# MEMORY.net
KiCad netlist of a schematic drawn in Altium Designer
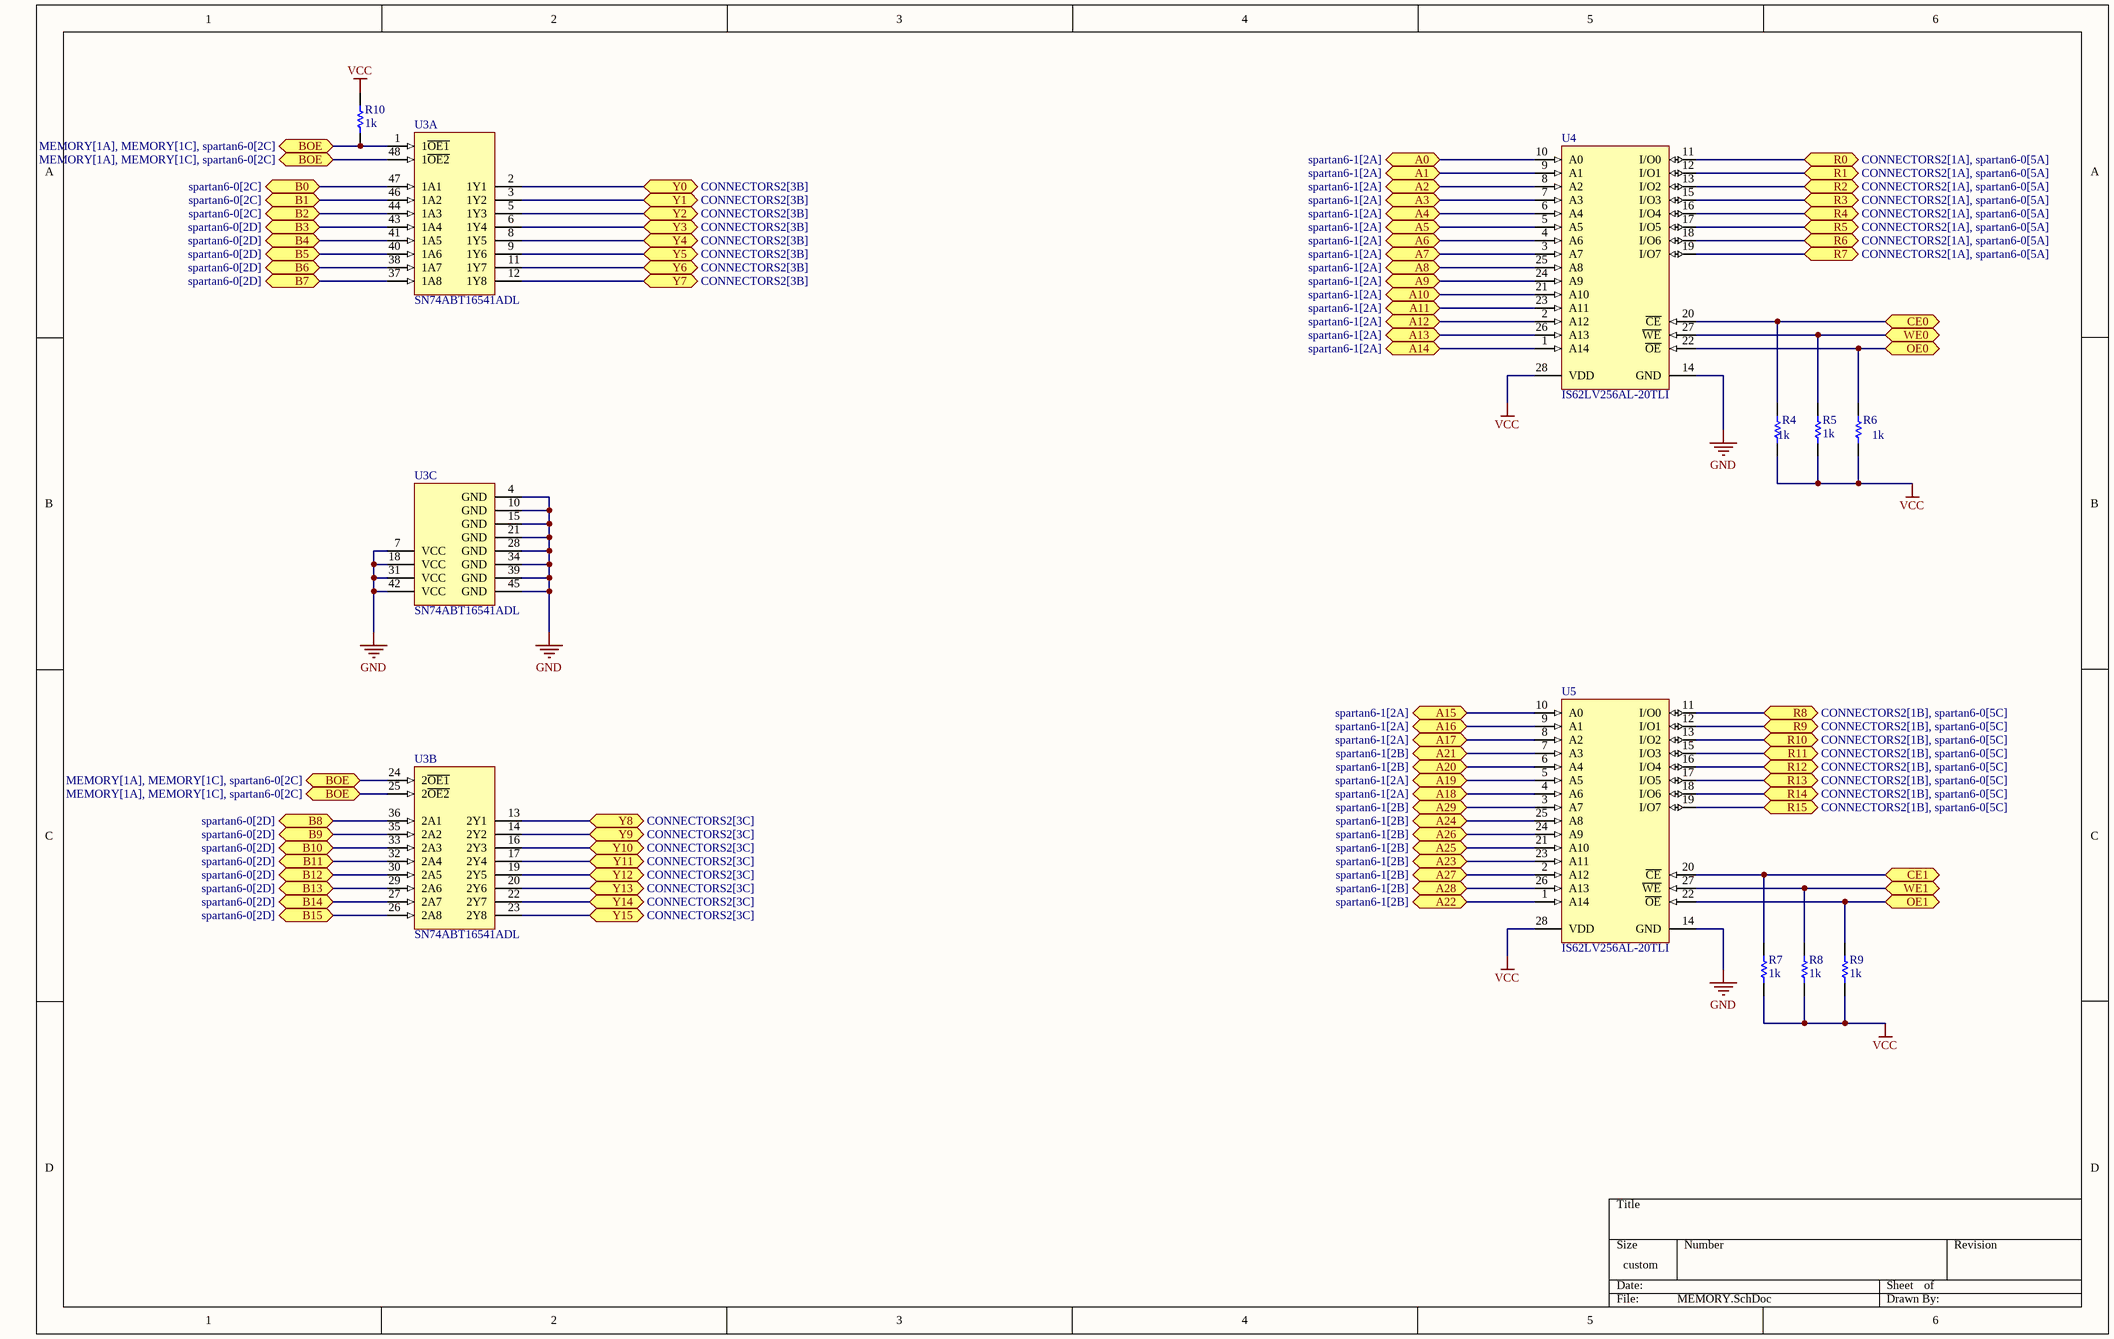
[diagram p0: MEMORY.SchDoc]

(export (version "E")
  (design (tool "Eeschema 10.0.6"))
  (components
    (comp (ref "R4")
      (value "1k")
      (footprint "RESC2013X60X35ML10T20")
      (fields (field (name "TOLERANCE") "5%") (field (name "MANUFACTURER") "Yageo"))
      (libsource (lib "Altium Content Vault") (part "RES-2"))
    )
    (comp (ref "R5")
      (value "1k")
      (footprint "RESC2013X60X35ML10T20")
      (fields (field (name "TOLERANCE") "5%") (field (name "MANUFACTURER") "Yageo"))
      (libsource (lib "Altium Content Vault") (part "RES-2"))
    )
    (comp (ref "R6")
      (value "1k")
      (footprint "RESC2013X60X35ML10T20")
      (fields (field (name "TOLERANCE") "5%") (field (name "MANUFACTURER") "Yageo"))
      (libsource (lib "Altium Content Vault") (part "RES-2"))
    )
    (comp (ref "R7")
      (value "1k")
      (footprint "RESC2013X60X35ML10T20")
      (fields (field (name "TOLERANCE") "5%") (field (name "MANUFACTURER") "Yageo"))
      (libsource (lib "Altium Content Vault") (part "RES-2"))
    )
    (comp (ref "R8")
      (value "1k")
      (footprint "RESC2013X60X35ML10T20")
      (fields (field (name "TOLERANCE") "5%") (field (name "MANUFACTURER") "Yageo"))
      (libsource (lib "Altium Content Vault") (part "RES-2"))
    )
    (comp (ref "R9")
      (value "1k")
      (footprint "RESC2013X60X35ML10T20")
      (fields (field (name "TOLERANCE") "5%") (field (name "MANUFACTURER") "Yageo"))
      (libsource (lib "Altium Content Vault") (part "RES-2"))
    )
    (comp (ref "R10")
      (value "1k")
      (footprint "RESC2013X60X35ML10T20")
      (fields (field (name "TOLERANCE") "5%") (field (name "MANUFACTURER") "Yageo"))
      (libsource (lib "Altium Content Vault") (part "RES-2"))
    )
    (comp (ref "U3")
      (value "SN74ABT16541ADL")
      (footprint "DL0048A_L")
      (description "16-Bit Buffers/Drivers With 3-State Outputs, DL0048A, TUBE")
      (fields
        (field (name "GENERIC PART NUMBER") "SN74ABT16541A")
        (field (name "MANUFACTURER") "Texas Instruments")
      )
      (libsource (lib "Altium Content Vault") (part "TI-74ACT_SN74XX16541X-48"))
    )
    (comp (ref "U4")
      (value "IS62LV256AL-20TLI")
      (footprint "ISSI-TSOP-1-28-8000X13400DE_N")
      (description "256 K Low Voltage CMOS SRAM, 32 K x 8, -40 to 85 degC, 28-Pin SOP (TSOP-1-28), Pb-Free")
      (fields (field (name "MANUFACTURER") "Integrated Silicon Solution Inc (ISSI)"))
      (libsource (lib "Altium Content Vault") (part "ISSI-IS62LV256AL-TSOP-1-28"))
    )
    (comp (ref "U5")
      (value "IS62LV256AL-20TLI")
      (footprint "ISSI-TSOP-1-28-8000X13400DE_N")
      (description "256 K Low Voltage CMOS SRAM, 32 K x 8, -40 to 85 degC, 28-Pin SOP (TSOP-1-28), Pb-Free")
      (fields (field (name "MANUFACTURER") "Integrated Silicon Solution Inc (ISSI)"))
      (libsource (lib "Altium Content Vault") (part "ISSI-IS62LV256AL-TSOP-1-28"))
    )
  )
  (nets
    (net (code "1") (name "/A0") (class "Default")
      (node (ref "U4") (pin "10") (pinfunction "A0_10") (pintype "input"))
    )
    (net (code "2") (name "/A1") (class "Default")
      (node (ref "U4") (pin "9") (pinfunction "A1_9") (pintype "input"))
    )
    (net (code "3") (name "/A2") (class "Default")
      (node (ref "U4") (pin "8") (pinfunction "A2_8") (pintype "input"))
    )
    (net (code "4") (name "/A3") (class "Default")
      (node (ref "U4") (pin "7") (pinfunction "A3_7") (pintype "input"))
    )
    (net (code "5") (name "/A4") (class "Default")
      (node (ref "U4") (pin "6") (pinfunction "A4_6") (pintype "input"))
    )
    (net (code "6") (name "/A5") (class "Default")
      (node (ref "U4") (pin "5") (pinfunction "A5_5") (pintype "input"))
    )
    (net (code "7") (name "/A6") (class "Default")
      (node (ref "U4") (pin "4") (pinfunction "A6_4") (pintype "input"))
    )
    (net (code "8") (name "/A7") (class "Default")
      (node (ref "U4") (pin "3") (pinfunction "A7_3") (pintype "input"))
    )
    (net (code "9") (name "/A8") (class "Default")
      (node (ref "U4") (pin "25") (pinfunction "A8_25") (pintype "input"))
    )
    (net (code "10") (name "/A9") (class "Default")
      (node (ref "U4") (pin "24") (pinfunction "A9_24") (pintype "input"))
    )
    (net (code "11") (name "/A10") (class "Default")
      (node (ref "U4") (pin "21") (pinfunction "A10_21") (pintype "input"))
    )
    (net (code "12") (name "/A11") (class "Default")
      (node (ref "U4") (pin "23") (pinfunction "A11_23") (pintype "input"))
    )
    (net (code "13") (name "/A12") (class "Default")
      (node (ref "U4") (pin "2") (pinfunction "A12_2") (pintype "input"))
    )
    (net (code "14") (name "/A13") (class "Default")
      (node (ref "U4") (pin "26") (pinfunction "A13_26") (pintype "input"))
    )
    (net (code "15") (name "/A14") (class "Default")
      (node (ref "U4") (pin "1") (pinfunction "A14_1") (pintype "input"))
    )
    (net (code "16") (name "/A15") (class "Default")
      (node (ref "U5") (pin "10") (pinfunction "A0_10") (pintype "input"))
    )
    (net (code "17") (name "/A16") (class "Default")
      (node (ref "U5") (pin "9") (pinfunction "A1_9") (pintype "input"))
    )
    (net (code "18") (name "/A17") (class "Default")
      (node (ref "U5") (pin "8") (pinfunction "A2_8") (pintype "input"))
    )
    (net (code "19") (name "/A18") (class "Default")
      (node (ref "U5") (pin "4") (pinfunction "A6_4") (pintype "input"))
    )
    (net (code "20") (name "/A19") (class "Default")
      (node (ref "U5") (pin "5") (pinfunction "A5_5") (pintype "input"))
    )
    (net (code "21") (name "/A20") (class "Default")
      (node (ref "U5") (pin "6") (pinfunction "A4_6") (pintype "input"))
    )
    (net (code "22") (name "/A21") (class "Default")
      (node (ref "U5") (pin "7") (pinfunction "A3_7") (pintype "input"))
    )
    (net (code "23") (name "/A22") (class "Default")
      (node (ref "U5") (pin "1") (pinfunction "A14_1") (pintype "input"))
    )
    (net (code "24") (name "/A23") (class "Default")
      (node (ref "U5") (pin "23") (pinfunction "A11_23") (pintype "input"))
    )
    (net (code "25") (name "/A24") (class "Default")
      (node (ref "U5") (pin "25") (pinfunction "A8_25") (pintype "input"))
    )
    (net (code "26") (name "/A25") (class "Default")
      (node (ref "U5") (pin "21") (pinfunction "A10_21") (pintype "input"))
    )
    (net (code "27") (name "/A26") (class "Default")
      (node (ref "U5") (pin "24") (pinfunction "A9_24") (pintype "input"))
    )
    (net (code "28") (name "/A27") (class "Default")
      (node (ref "U5") (pin "2") (pinfunction "A12_2") (pintype "input"))
    )
    (net (code "29") (name "/A28") (class "Default")
      (node (ref "U5") (pin "26") (pinfunction "A13_26") (pintype "input"))
    )
    (net (code "30") (name "/A29") (class "Default")
      (node (ref "U5") (pin "3") (pinfunction "A7_3") (pintype "input"))
    )
    (net (code "31") (name "/B0") (class "Default")
      (node (ref "U3") (pin "47") (pinfunction "1A1_47") (pintype "input"))
    )
    (net (code "32") (name "/B1") (class "Default")
      (node (ref "U3") (pin "46") (pinfunction "1A2_46") (pintype "input"))
    )
    (net (code "33") (name "/B2") (class "Default")
      (node (ref "U3") (pin "44") (pinfunction "1A3_44") (pintype "input"))
    )
    (net (code "34") (name "/B3") (class "Default")
      (node (ref "U3") (pin "43") (pinfunction "1A4_43") (pintype "input"))
    )
    (net (code "35") (name "/B4") (class "Default")
      (node (ref "U3") (pin "41") (pinfunction "1A5_41") (pintype "input"))
    )
    (net (code "36") (name "/B5") (class "Default")
      (node (ref "U3") (pin "40") (pinfunction "1A6_40") (pintype "input"))
    )
    (net (code "37") (name "/B6") (class "Default")
      (node (ref "U3") (pin "38") (pinfunction "1A7_38") (pintype "input"))
    )
    (net (code "38") (name "/B7") (class "Default")
      (node (ref "U3") (pin "37") (pinfunction "1A8_37") (pintype "input"))
    )
    (net (code "39") (name "/B8") (class "Default")
      (node (ref "U3") (pin "36") (pinfunction "2A1_36") (pintype "input"))
    )
    (net (code "40") (name "/B9") (class "Default")
      (node (ref "U3") (pin "35") (pinfunction "2A2_35") (pintype "input"))
    )
    (net (code "41") (name "/B10") (class "Default")
      (node (ref "U3") (pin "33") (pinfunction "2A3_33") (pintype "input"))
    )
    (net (code "42") (name "/B11") (class "Default")
      (node (ref "U3") (pin "32") (pinfunction "2A4_32") (pintype "input"))
    )
    (net (code "43") (name "/B12") (class "Default")
      (node (ref "U3") (pin "30") (pinfunction "2A5_30") (pintype "input"))
    )
    (net (code "44") (name "/B13") (class "Default")
      (node (ref "U3") (pin "29") (pinfunction "2A6_29") (pintype "input"))
    )
    (net (code "45") (name "/B14") (class "Default")
      (node (ref "U3") (pin "27") (pinfunction "2A7_27") (pintype "input"))
    )
    (net (code "46") (name "/B15") (class "Default")
      (node (ref "U3") (pin "26") (pinfunction "2A8_26") (pintype "input"))
    )
    (net (code "47") (name "/BOE") (class "Default")
      (node (ref "R10") (pin "2") (pinfunction "2_2") (pintype "passive"))
      (node (ref "U3") (pin "1") (pinfunction "1~{OE1}_1") (pintype "input"))
      (node (ref "U3") (pin "24") (pinfunction "2~{OE1}_24") (pintype "input"))
      (node (ref "U3") (pin "25") (pinfunction "2~{OE2}_25") (pintype "input"))
      (node (ref "U3") (pin "48") (pinfunction "1~{OE2}_48") (pintype "input"))
    )
    (net (code "48") (name "/CE0") (class "Default")
      (node (ref "R4") (pin "1") (pinfunction "1_1") (pintype "passive"))
      (node (ref "U4") (pin "20") (pinfunction "~{CE}_20") (pintype "input"))
    )
    (net (code "49") (name "/CE1") (class "Default")
      (node (ref "R7") (pin "1") (pinfunction "1_1") (pintype "passive"))
      (node (ref "U5") (pin "20") (pinfunction "~{CE}_20") (pintype "input"))
    )
    (net (code "50") (name "/OE0") (class "Default")
      (node (ref "R6") (pin "1") (pinfunction "1_1") (pintype "passive"))
      (node (ref "U4") (pin "22") (pinfunction "~{OE}_22") (pintype "input"))
    )
    (net (code "51") (name "/OE1") (class "Default")
      (node (ref "R9") (pin "1") (pinfunction "1_1") (pintype "passive"))
      (node (ref "U5") (pin "22") (pinfunction "~{OE}_22") (pintype "input"))
    )
    (net (code "52") (name "/R0") (class "Default")
      (node (ref "U4") (pin "11") (pinfunction "I/O0_11") (pintype "bidirectional"))
    )
    (net (code "53") (name "/R1") (class "Default")
      (node (ref "U4") (pin "12") (pinfunction "I/O1_12") (pintype "bidirectional"))
    )
    (net (code "54") (name "/R2") (class "Default")
      (node (ref "U4") (pin "13") (pinfunction "I/O2_13") (pintype "bidirectional"))
    )
    (net (code "55") (name "/R3") (class "Default")
      (node (ref "U4") (pin "15") (pinfunction "I/O3_15") (pintype "bidirectional"))
    )
    (net (code "56") (name "/R4") (class "Default")
      (node (ref "U4") (pin "16") (pinfunction "I/O4_16") (pintype "bidirectional"))
    )
    (net (code "57") (name "/R5") (class "Default")
      (node (ref "U4") (pin "17") (pinfunction "I/O5_17") (pintype "bidirectional"))
    )
    (net (code "58") (name "/R6") (class "Default")
      (node (ref "U4") (pin "18") (pinfunction "I/O6_18") (pintype "bidirectional"))
    )
    (net (code "59") (name "/R7") (class "Default")
      (node (ref "U4") (pin "19") (pinfunction "I/O7_19") (pintype "bidirectional"))
    )
    (net (code "60") (name "/R8") (class "Default")
      (node (ref "U5") (pin "11") (pinfunction "I/O0_11") (pintype "bidirectional"))
    )
    (net (code "61") (name "/R9") (class "Default")
      (node (ref "U5") (pin "12") (pinfunction "I/O1_12") (pintype "bidirectional"))
    )
    (net (code "62") (name "/R10") (class "Default")
      (node (ref "U5") (pin "13") (pinfunction "I/O2_13") (pintype "bidirectional"))
    )
    (net (code "63") (name "/R11") (class "Default")
      (node (ref "U5") (pin "15") (pinfunction "I/O3_15") (pintype "bidirectional"))
    )
    (net (code "64") (name "/R12") (class "Default")
      (node (ref "U5") (pin "16") (pinfunction "I/O4_16") (pintype "bidirectional"))
    )
    (net (code "65") (name "/R13") (class "Default")
      (node (ref "U5") (pin "17") (pinfunction "I/O5_17") (pintype "bidirectional"))
    )
    (net (code "66") (name "/R14") (class "Default")
      (node (ref "U5") (pin "18") (pinfunction "I/O6_18") (pintype "bidirectional"))
    )
    (net (code "67") (name "/R15") (class "Default")
      (node (ref "U5") (pin "19") (pinfunction "I/O7_19") (pintype "bidirectional"))
    )
    (net (code "68") (name "/WE0") (class "Default")
      (node (ref "R5") (pin "1") (pinfunction "1_1") (pintype "passive"))
      (node (ref "U4") (pin "27") (pinfunction "~{WE}_27") (pintype "input"))
    )
    (net (code "69") (name "/WE1") (class "Default")
      (node (ref "R8") (pin "1") (pinfunction "1_1") (pintype "passive"))
      (node (ref "U5") (pin "27") (pinfunction "~{WE}_27") (pintype "input"))
    )
    (net (code "70") (name "/Y0") (class "Default")
      (node (ref "U3") (pin "2") (pinfunction "1Y1_2") (pintype "tri_state"))
    )
    (net (code "71") (name "/Y1") (class "Default")
      (node (ref "U3") (pin "3") (pinfunction "1Y2_3") (pintype "tri_state"))
    )
    (net (code "72") (name "/Y2") (class "Default")
      (node (ref "U3") (pin "5") (pinfunction "1Y3_5") (pintype "tri_state"))
    )
    (net (code "73") (name "/Y3") (class "Default")
      (node (ref "U3") (pin "6") (pinfunction "1Y4_6") (pintype "tri_state"))
    )
    (net (code "74") (name "/Y4") (class "Default")
      (node (ref "U3") (pin "8") (pinfunction "1Y5_8") (pintype "tri_state"))
    )
    (net (code "75") (name "/Y5") (class "Default")
      (node (ref "U3") (pin "9") (pinfunction "1Y6_9") (pintype "tri_state"))
    )
    (net (code "76") (name "/Y6") (class "Default")
      (node (ref "U3") (pin "11") (pinfunction "1Y7_11") (pintype "tri_state"))
    )
    (net (code "77") (name "/Y7") (class "Default")
      (node (ref "U3") (pin "12") (pinfunction "1Y8_12") (pintype "tri_state"))
    )
    (net (code "78") (name "/Y8") (class "Default")
      (node (ref "U3") (pin "13") (pinfunction "2Y1_13") (pintype "tri_state"))
    )
    (net (code "79") (name "/Y9") (class "Default")
      (node (ref "U3") (pin "14") (pinfunction "2Y2_14") (pintype "tri_state"))
    )
    (net (code "80") (name "/Y10") (class "Default")
      (node (ref "U3") (pin "16") (pinfunction "2Y3_16") (pintype "tri_state"))
    )
    (net (code "81") (name "/Y11") (class "Default")
      (node (ref "U3") (pin "17") (pinfunction "2Y4_17") (pintype "tri_state"))
    )
    (net (code "82") (name "/Y12") (class "Default")
      (node (ref "U3") (pin "19") (pinfunction "2Y5_19") (pintype "tri_state"))
    )
    (net (code "83") (name "/Y13") (class "Default")
      (node (ref "U3") (pin "20") (pinfunction "2Y6_20") (pintype "tri_state"))
    )
    (net (code "84") (name "/Y14") (class "Default")
      (node (ref "U3") (pin "22") (pinfunction "2Y7_22") (pintype "tri_state"))
    )
    (net (code "85") (name "/Y15") (class "Default")
      (node (ref "U3") (pin "23") (pinfunction "2Y8_23") (pintype "tri_state"))
    )
    (net (code "86") (name "GND") (class "Default")
      (node (ref "U3") (pin "10") (pinfunction "GND_10") (pintype "power_in"))
      (node (ref "U3") (pin "15") (pinfunction "GND_15") (pintype "power_in"))
      (node (ref "U3") (pin "18") (pinfunction "VCC_18") (pintype "power_in"))
      (node (ref "U3") (pin "21") (pinfunction "GND_21") (pintype "power_in"))
      (node (ref "U3") (pin "28") (pinfunction "GND_28") (pintype "power_in"))
      (node (ref "U3") (pin "31") (pinfunction "VCC_31") (pintype "power_in"))
      (node (ref "U3") (pin "34") (pinfunction "GND_34") (pintype "power_in"))
      (node (ref "U3") (pin "39") (pinfunction "GND_39") (pintype "power_in"))
      (node (ref "U3") (pin "4") (pinfunction "GND_4") (pintype "power_in"))
      (node (ref "U3") (pin "42") (pinfunction "VCC_42") (pintype "power_in"))
      (node (ref "U3") (pin "45") (pinfunction "GND_45") (pintype "power_in"))
      (node (ref "U3") (pin "7") (pinfunction "VCC_7") (pintype "power_in"))
      (node (ref "U4") (pin "14") (pinfunction "GND_14") (pintype "power_in"))
      (node (ref "U5") (pin "14") (pinfunction "GND_14") (pintype "power_in"))
    )
    (net (code "87") (name "VCC") (class "Default")
      (node (ref "R10") (pin "1") (pinfunction "1_1") (pintype "passive"))
      (node (ref "R4") (pin "2") (pinfunction "2_2") (pintype "passive"))
      (node (ref "R5") (pin "2") (pinfunction "2_2") (pintype "passive"))
      (node (ref "R6") (pin "2") (pinfunction "2_2") (pintype "passive"))
      (node (ref "R7") (pin "2") (pinfunction "2_2") (pintype "passive"))
      (node (ref "R8") (pin "2") (pinfunction "2_2") (pintype "passive"))
      (node (ref "R9") (pin "2") (pinfunction "2_2") (pintype "passive"))
      (node (ref "U4") (pin "28") (pinfunction "VDD_28") (pintype "power_in"))
      (node (ref "U5") (pin "28") (pinfunction "VDD_28") (pintype "power_in"))
    )
  )
)
